# Peripheral.net
KiCad netlist of a schematic drawn in Altium Designer
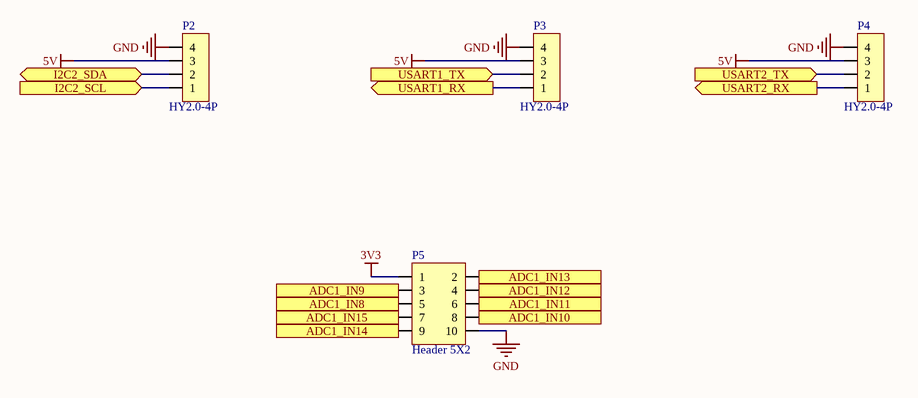
[diagram p0: Peripheral.SchDoc]

(export (version "E")
  (design (tool "Eeschema 10.0.6"))
  (components
    (comp (ref "P2")
      (value "HY2.0-4P")
      (footprint "HY2.0-4P-RA")
      (description "Header, 4-Pin")
      (libsource (lib "BKIT4U_LIB") (part "Header 4"))
    )
    (comp (ref "P3")
      (value "HY2.0-4P")
      (footprint "HY2.0-4P-RA")
      (description "Header, 4-Pin")
      (libsource (lib "BKIT4U_LIB") (part "Header 4"))
    )
    (comp (ref "P4")
      (value "HY2.0-4P")
      (footprint "HY2.0-4P-RA")
      (description "Header, 4-Pin")
      (libsource (lib "BKIT4U_LIB") (part "Header 4"))
    )
    (comp (ref "P5")
      (value "Header 5X2")
      (footprint "DC3-10P-1.27MM-RA")
      (description "Header, 5-Pin, Dual row")
      (fields (field (name "PUBLISHER") "Altium Limited"))
      (libsource (lib "BKIT4U_LIB") (part "Header 5X2"))
    )
  )
  (nets
    (net (code "1") (name "/ADC1_IN8") (class "Default")
      (node (ref "P5") (pin "5") (pinfunction "5_5") (pintype "passive"))
    )
    (net (code "2") (name "/ADC1_IN9") (class "Default")
      (node (ref "P5") (pin "3") (pinfunction "3_3") (pintype "passive"))
    )
    (net (code "3") (name "/ADC1_IN10") (class "Default")
      (node (ref "P5") (pin "8") (pinfunction "8_8") (pintype "passive"))
    )
    (net (code "4") (name "/ADC1_IN11") (class "Default")
      (node (ref "P5") (pin "6") (pinfunction "6_6") (pintype "passive"))
    )
    (net (code "5") (name "/ADC1_IN12") (class "Default")
      (node (ref "P5") (pin "4") (pinfunction "4_4") (pintype "passive"))
    )
    (net (code "6") (name "/ADC1_IN13") (class "Default")
      (node (ref "P5") (pin "2") (pinfunction "2_2") (pintype "passive"))
    )
    (net (code "7") (name "/ADC1_IN14") (class "Default")
      (node (ref "P5") (pin "9") (pinfunction "9_9") (pintype "passive"))
    )
    (net (code "8") (name "/ADC1_IN15") (class "Default")
      (node (ref "P5") (pin "7") (pinfunction "7_7") (pintype "passive"))
    )
    (net (code "9") (name "/I2C2_SCL") (class "Default")
      (node (ref "P2") (pin "1") (pinfunction "1_1") (pintype "passive"))
    )
    (net (code "10") (name "/I2C2_SDA") (class "Default")
      (node (ref "P2") (pin "2") (pinfunction "2_2") (pintype "passive"))
    )
    (net (code "11") (name "/USART1_RX") (class "Default")
      (node (ref "P3") (pin "1") (pinfunction "1_1") (pintype "passive"))
    )
    (net (code "12") (name "/USART1_TX") (class "Default")
      (node (ref "P3") (pin "2") (pinfunction "2_2") (pintype "passive"))
    )
    (net (code "13") (name "/USART2_RX") (class "Default")
      (node (ref "P4") (pin "1") (pinfunction "1_1") (pintype "passive"))
    )
    (net (code "14") (name "/USART2_TX") (class "Default")
      (node (ref "P4") (pin "2") (pinfunction "2_2") (pintype "passive"))
    )
    (net (code "15") (name "3V3") (class "Default")
      (node (ref "P5") (pin "1") (pinfunction "1_1") (pintype "passive"))
    )
    (net (code "16") (name "5V") (class "Default")
      (node (ref "P2") (pin "3") (pinfunction "3_3") (pintype "passive"))
      (node (ref "P3") (pin "3") (pinfunction "3_3") (pintype "passive"))
      (node (ref "P4") (pin "3") (pinfunction "3_3") (pintype "passive"))
    )
    (net (code "17") (name "GND") (class "Default")
      (node (ref "P2") (pin "4") (pinfunction "4_4") (pintype "passive"))
      (node (ref "P3") (pin "4") (pinfunction "4_4") (pintype "passive"))
      (node (ref "P4") (pin "4") (pinfunction "4_4") (pintype "passive"))
      (node (ref "P5") (pin "10") (pinfunction "10_10") (pintype "passive"))
    )
  )
)
